# CH32X035G8U6-R0.net
KiCad netlist of a schematic drawn in Altium Designer
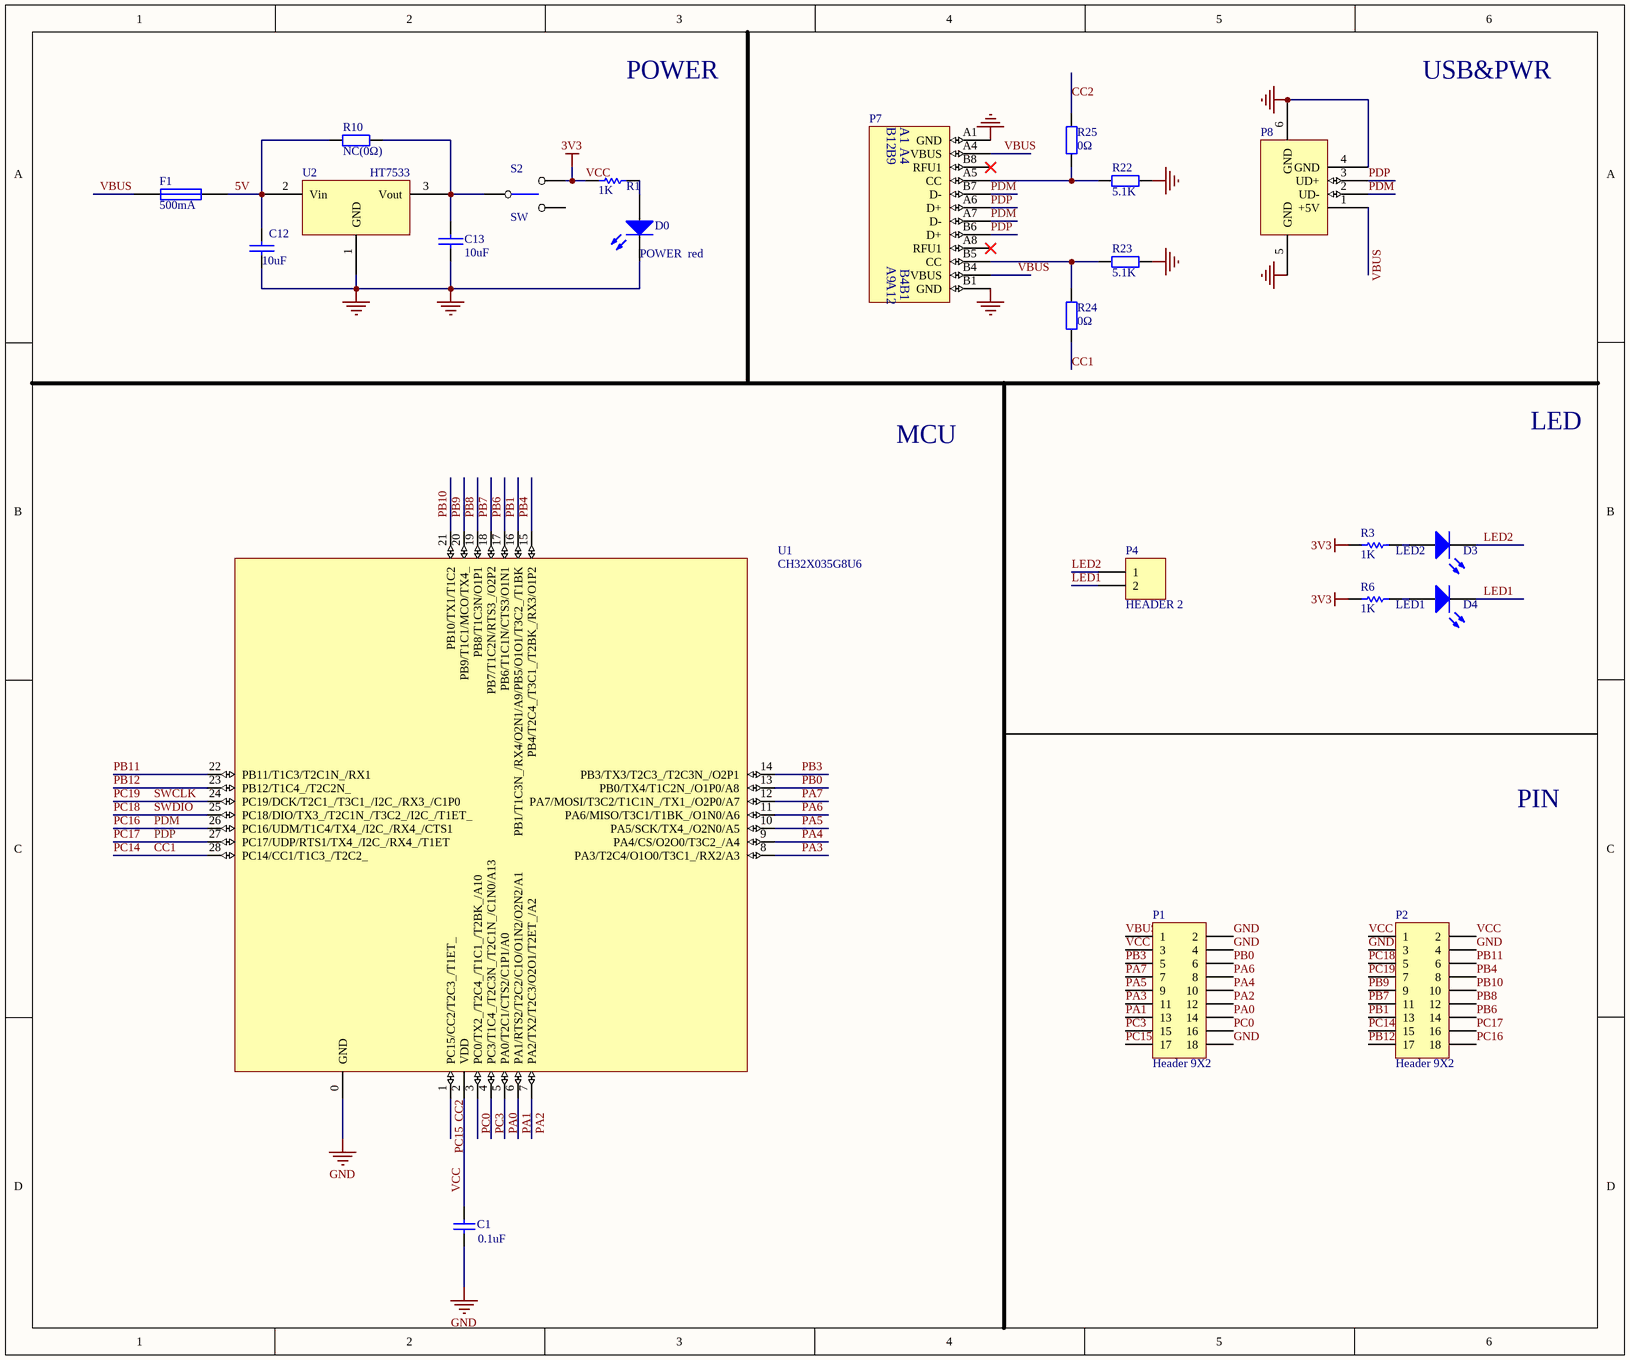
[diagram p0: CH32X035G8U6-R0.SchDoc]

(export (version "E")
  (design (tool "Eeschema 10.0.6"))
  (components
    (comp (ref "C1")
      (value "0.1uF")
      (footprint "0603_C")
      (description "Capacitor")
      (libsource (lib "Miscellaneous Devices") (part "Cap"))
    )
    (comp (ref "C12")
      (value "10uF")
      (footprint "0603_C")
      (description "Capacitor")
      (libsource (lib "*") (part "CAP"))
    )
    (comp (ref "C13")
      (value "10uF")
      (footprint "0603_C")
      (description "Capacitor")
      (libsource (lib "*") (part "CAP"))
    )
    (comp (ref "D0")
      (value "POWER  red")
      (footprint "0603+")
      (description "Typical INFRARED GaAs LED")
      (fields (field (name "PUBLISHER") "Altium Limited"))
      (libsource (lib "*") (part "LED0"))
    )
    (comp (ref "D3")
      (value "LED2")
      (footprint "0603+")
      (description "Typical INFRARED GaAs LED")
      (fields (field (name "PUBLISHER") "Altium Limited"))
      (libsource (lib "*") (part "LED0"))
    )
    (comp (ref "D4")
      (value "LED1")
      (footprint "0603+")
      (description "Typical INFRARED GaAs LED")
      (fields (field (name "PUBLISHER") "Altium Limited"))
      (libsource (lib "*") (part "LED0"))
    )
    (comp (ref "F1")
      (value "500mA")
      (footprint "0603")
      (description "Fuse")
      (libsource (lib "*") (part "FUSE1"))
    )
    (comp (ref "P1")
      (value "Header 9X2")
      (footprint "IDC18-2.54mm")
      (description "Header, 9-Pin, Dual row")
      (fields (field (name "PUBLISHER") "Altium Limited"))
      (libsource (lib "Miscellaneous Connectors") (part "Header 9X2"))
    )
    (comp (ref "P2")
      (value "Header 9X2")
      (footprint "IDC18-2.54mm")
      (description "Header, 9-Pin, Dual row")
      (fields (field (name "PUBLISHER") "Altium Limited"))
      (libsource (lib "Miscellaneous Connectors") (part "Header 9X2"))
    )
    (comp (ref "P4")
      (value "HEADER 2")
      (footprint "MYPCB:SIP2-2.54mm")
      (description "Header, 2-Pin")
      (libsource (lib "wch_sch_others") (part "HEADER 2"))
    )
    (comp (ref "P7")
      (value "TYPE-C")
      (footprint "TYPE-C-Receptacle-2.0")
      (libsource (lib "*") (part "TYPE-C1"))
    )
    (comp (ref "P8")
      (value "USB_A")
      (footprint "USBAF")
      (description "USB Port")
      (libsource (lib "*") (part "USB"))
    )
    (comp (ref "R1")
      (value "1K")
      (footprint "0603")
      (description "Semiconductor Resistor")
      (fields (field (name "PUBLISHER") "Altium Limited"))
      (libsource (lib "*") (part "Res Semi"))
    )
    (comp (ref "R3")
      (value "1K")
      (footprint "0603")
      (description "Semiconductor Resistor")
      (fields (field (name "PUBLISHER") "Altium Limited"))
      (libsource (lib "*") (part "Res Semi"))
    )
    (comp (ref "R6")
      (value "1K")
      (footprint "0603")
      (description "Semiconductor Resistor")
      (fields (field (name "PUBLISHER") "Altium Limited"))
      (libsource (lib "*") (part "Res Semi"))
    )
    (comp (ref "R10")
      (value "NC(0Ω)")
      (footprint "0603")
      (description "Resistor")
      (fields (field (name "PUBLISHER") "Altium Limited"))
      (libsource (lib "*") (part "Res2"))
    )
    (comp (ref "R22")
      (value "5.1K")
      (footprint "0603")
      (description "Resistor")
      (libsource (lib "") (part "Res2_1"))
    )
    (comp (ref "R23")
      (value "5.1K")
      (footprint "0603")
      (description "Resistor")
      (libsource (lib "") (part "Res2_1"))
    )
    (comp (ref "R24")
      (value "0Ω")
      (footprint "0603")
      (description "Resistor")
      (libsource (lib "Miscellaneous Devices") (part "Res2"))
    )
    (comp (ref "R25")
      (value "0Ω")
      (footprint "0603")
      (description "Resistor")
      (libsource (lib "Miscellaneous Devices") (part "Res2"))
    )
    (comp (ref "S2") (value "SW") (footprint "SW1") (libsource (lib "*") (part "SW")))
    (comp (ref "U1")
      (value "CH32X035G8U6")
      (footprint "QFN28_4X4")
      (description "RISC-V MCU with USB/PD/ADC/SPI/I2C/UART/OA/CMP")
      (libsource (lib "CHXXX") (part "CH32X035G8U6"))
    )
    (comp (ref "U2")
      (value "HT7533")
      (footprint "SOT-89")
      (libsource (lib "wch_sch_others") (part "1117-3.3V"))
    )
  )
  (nets
    (net (code "1") (name "/5V") (class "Default")
      (node (ref "C12") (pin "1") (pinfunction "1_1") (pintype "passive"))
      (node (ref "F1") (pin "2") (pinfunction "2_2") (pintype "passive"))
      (node (ref "R10") (pin "2") (pinfunction "2_2") (pintype "passive"))
      (node (ref "U2") (pin "2") (pinfunction "Vin_2") (pintype "passive"))
    )
    (net (code "3") (name "/CC1") (class "Default")
      (node (ref "P2") (pin "15") (pinfunction "15_15") (pintype "passive"))
      (node (ref "R24") (pin "1") (pinfunction "1_1") (pintype "passive"))
      (node (ref "U1") (pin "28") (pinfunction "PC14/CC1/T1C3_/T2C2__28") (pintype "bidirectional"))
    )
    (net (code "4") (name "/CC2") (class "Default")
      (node (ref "P1") (pin "17") (pinfunction "17_17") (pintype "passive"))
      (node (ref "R25") (pin "2") (pinfunction "2_2") (pintype "passive"))
      (node (ref "U1") (pin "1") (pinfunction "PC15/CC2/T2C3_/T1ET__1") (pintype "bidirectional"))
    )
    (net (code "5") (name "/LED1") (class "Default")
      (node (ref "D4") (pin "2") (pinfunction "K_2") (pintype "passive"))
      (node (ref "P4") (pin "2") (pinfunction "2_2") (pintype "passive"))
    )
    (net (code "6") (name "/LED2") (class "Default")
      (node (ref "D3") (pin "2") (pinfunction "K_2") (pintype "passive"))
      (node (ref "P4") (pin "1") (pinfunction "1_1") (pintype "passive"))
    )
    (net (code "7") (name "/PA0") (class "Default")
      (node (ref "P1") (pin "14") (pinfunction "14_14") (pintype "passive"))
      (node (ref "U1") (pin "5") (pinfunction "PA0/T2C1/CTS2/C1P1/A0_5") (pintype "bidirectional"))
    )
    (net (code "8") (name "/PA1") (class "Default")
      (node (ref "P1") (pin "13") (pinfunction "13_13") (pintype "passive"))
      (node (ref "U1") (pin "6") (pinfunction "PA1/RTS2/T2C2/C1O/O1N2/O2N2/A1_6") (pintype "bidirectional"))
    )
    (net (code "9") (name "/PA2") (class "Default")
      (node (ref "P1") (pin "12") (pinfunction "12_12") (pintype "passive"))
      (node (ref "U1") (pin "7") (pinfunction "PA2/TX2/T2C3/O2O1/T2ET_/A2_7") (pintype "bidirectional"))
    )
    (net (code "10") (name "/PA3") (class "Default")
      (node (ref "P1") (pin "11") (pinfunction "11_11") (pintype "passive"))
      (node (ref "U1") (pin "8") (pinfunction "PA3/T2C4/O1O0/T3C1_/RX2/A3_8") (pintype "bidirectional"))
    )
    (net (code "11") (name "/PA4") (class "Default")
      (node (ref "P1") (pin "10") (pinfunction "10_10") (pintype "passive"))
      (node (ref "U1") (pin "9") (pinfunction "PA4/CS/O2O0/T3C2_/A4_9") (pintype "bidirectional"))
    )
    (net (code "12") (name "/PA5") (class "Default")
      (node (ref "P1") (pin "9") (pinfunction "9_9") (pintype "passive"))
      (node (ref "U1") (pin "10") (pinfunction "PA5/SCK/TX4_/O2N0/A5_10") (pintype "bidirectional"))
    )
    (net (code "13") (name "/PA6") (class "Default")
      (node (ref "P1") (pin "8") (pinfunction "8_8") (pintype "passive"))
      (node (ref "U1") (pin "11") (pinfunction "PA6/MISO/T3C1/T1BK_/O1N0/A6_11") (pintype "bidirectional"))
    )
    (net (code "14") (name "/PA7") (class "Default")
      (node (ref "P1") (pin "7") (pinfunction "7_7") (pintype "passive"))
      (node (ref "U1") (pin "12") (pinfunction "PA7/MOSI/T3C2/T1C1N_/TX1_/O2P0/A7_12") (pintype "bidirectional"))
    )
    (net (code "15") (name "/PB0") (class "Default")
      (node (ref "P1") (pin "6") (pinfunction "6_6") (pintype "passive"))
      (node (ref "U1") (pin "13") (pinfunction "PB0/TX4/T1C2N_/O1P0/A8_13") (pintype "bidirectional"))
    )
    (net (code "16") (name "/PB1") (class "Default")
      (node (ref "P2") (pin "13") (pinfunction "13_13") (pintype "passive"))
      (node (ref "U1") (pin "16") (pinfunction "PB1/T1C3N_/RX4/O2N1/A9/PB5/O1O1/T3C2_/T1BK_16") (pintype "bidirectional"))
    )
    (net (code "17") (name "/PB3") (class "Default")
      (node (ref "P1") (pin "5") (pinfunction "5_5") (pintype "passive"))
      (node (ref "U1") (pin "14") (pinfunction "PB3/TX3/T2C3_/T2C3N_/O2P1_14") (pintype "bidirectional"))
    )
    (net (code "18") (name "/PB4") (class "Default")
      (node (ref "P2") (pin "8") (pinfunction "8_8") (pintype "passive"))
      (node (ref "U1") (pin "15") (pinfunction "PB4/T2C4_/T3C1_/T2BK_/RX3/O1P2_15") (pintype "bidirectional"))
    )
    (net (code "19") (name "/PB6") (class "Default")
      (node (ref "P2") (pin "14") (pinfunction "14_14") (pintype "passive"))
      (node (ref "U1") (pin "17") (pinfunction "PB6/T1C1N/CTS3/O1N1_17") (pintype "bidirectional"))
    )
    (net (code "20") (name "/PB7") (class "Default")
      (node (ref "P2") (pin "11") (pinfunction "11_11") (pintype "passive"))
      (node (ref "U1") (pin "18") (pinfunction "PB7/T1C2N/RTS3_/O2P2_18") (pintype "bidirectional"))
    )
    (net (code "21") (name "/PB8") (class "Default")
      (node (ref "P2") (pin "12") (pinfunction "12_12") (pintype "passive"))
      (node (ref "U1") (pin "19") (pinfunction "PB8/T1C3N/O1P1_19") (pintype "bidirectional"))
    )
    (net (code "22") (name "/PB9") (class "Default")
      (node (ref "P2") (pin "9") (pinfunction "9_9") (pintype "passive"))
      (node (ref "U1") (pin "20") (pinfunction "PB9/T1C1/MCO/TX4__20") (pintype "bidirectional"))
    )
    (net (code "23") (name "/PB10") (class "Default")
      (node (ref "P2") (pin "10") (pinfunction "10_10") (pintype "passive"))
      (node (ref "U1") (pin "21") (pinfunction "PB10/TX1/T1C2_21") (pintype "bidirectional"))
    )
    (net (code "24") (name "/PB11") (class "Default")
      (node (ref "P2") (pin "6") (pinfunction "6_6") (pintype "passive"))
      (node (ref "U1") (pin "22") (pinfunction "PB11/T1C3/T2C1N_/RX1_22") (pintype "bidirectional"))
    )
    (net (code "25") (name "/PB12") (class "Default")
      (node (ref "P2") (pin "17") (pinfunction "17_17") (pintype "passive"))
      (node (ref "U1") (pin "23") (pinfunction "PB12/T1C4_/T2C2N__23") (pintype "bidirectional"))
    )
    (net (code "26") (name "/PC0") (class "Default")
      (node (ref "P1") (pin "16") (pinfunction "16_16") (pintype "passive"))
      (node (ref "U1") (pin "3") (pinfunction "PC0/TX2_/T2C4_/T1C1_/T2BK_/A10_3") (pintype "bidirectional"))
    )
    (net (code "27") (name "/PC3") (class "Default")
      (node (ref "P1") (pin "15") (pinfunction "15_15") (pintype "passive"))
      (node (ref "U1") (pin "4") (pinfunction "PC3/T1C4_/T2C3N_/T2C1N_/C1N0/A13_4") (pintype "bidirectional"))
    )
    (net (code "28") (name "/PC16") (class "Default")
      (node (ref "P2") (pin "18") (pinfunction "18_18") (pintype "passive"))
      (node (ref "P7") (pin "A7") (pinfunction "D-_A7") (pintype "bidirectional"))
      (node (ref "P7") (pin "B7") (pinfunction "D-_B7") (pintype "bidirectional"))
      (node (ref "P8") (pin "2") (pinfunction "UD-_2") (pintype "bidirectional"))
      (node (ref "U1") (pin "26") (pinfunction "PC16/UDM/T1C4/TX4_/I2C_/RX4_/CTS1_26") (pintype "bidirectional"))
    )
    (net (code "29") (name "/PC17") (class "Default")
      (node (ref "P2") (pin "16") (pinfunction "16_16") (pintype "passive"))
      (node (ref "P7") (pin "A6") (pinfunction "D+_A6") (pintype "bidirectional"))
      (node (ref "P7") (pin "B6") (pinfunction "D+_B6") (pintype "bidirectional"))
      (node (ref "P8") (pin "3") (pinfunction "UD+_3") (pintype "bidirectional"))
      (node (ref "U1") (pin "27") (pinfunction "PC17/UDP/RTS1/TX4_/I2C_/RX4_/T1ET_27") (pintype "bidirectional"))
    )
    (net (code "30") (name "/PC18") (class "Default")
      (node (ref "P2") (pin "5") (pinfunction "5_5") (pintype "passive"))
      (node (ref "U1") (pin "25") (pinfunction "PC18/DIO/TX3_/T2C1N_/T3C2_/I2C_/T1ET__25") (pintype "bidirectional"))
    )
    (net (code "31") (name "/PC19") (class "Default")
      (node (ref "P2") (pin "7") (pinfunction "7_7") (pintype "passive"))
      (node (ref "U1") (pin "24") (pinfunction "PC19/DCK/T2C1_/T3C1_/I2C_/RX3_/C1P0_24") (pintype "bidirectional"))
    )
    (net (code "32") (name "/VBUS") (class "Default")
      (node (ref "F1") (pin "1") (pinfunction "1_1") (pintype "passive"))
      (node (ref "P1") (pin "1") (pinfunction "1_1") (pintype "passive"))
      (node (ref "P7") (pin "A4") (pinfunction "VBUS_A4") (pintype "bidirectional"))
      (node (ref "P7") (pin "B4") (pinfunction "VBUS_B4") (pintype "bidirectional"))
      (node (ref "P8") (pin "1") (pinfunction "+5V_1") (pintype "power_in"))
    )
    (net (code "33") (name "3V3") (class "Default")
      (node (ref "C1") (pin "2") (pinfunction "2_2") (pintype "passive"))
      (node (ref "P1") (pin "3") (pinfunction "3_3") (pintype "passive"))
      (node (ref "P2") (pin "1") (pinfunction "1_1") (pintype "passive"))
      (node (ref "P2") (pin "2") (pinfunction "2_2") (pintype "passive"))
      (node (ref "R1") (pin "2") (pinfunction "2_2") (pintype "passive"))
      (node (ref "R3") (pin "1") (pinfunction "1_1") (pintype "passive"))
      (node (ref "R6") (pin "1") (pinfunction "1_1") (pintype "passive"))
      (node (ref "S2") (pin "3") (pinfunction "3_3") (pintype "passive"))
      (node (ref "U1") (pin "2") (pinfunction "VDD_2") (pintype "power_in"))
    )
    (net (code "34") (name "GND") (class "Default")
      (node (ref "C1") (pin "1") (pinfunction "1_1") (pintype "passive"))
      (node (ref "C12") (pin "2") (pinfunction "2_2") (pintype "passive"))
      (node (ref "C13") (pin "2") (pinfunction "2_2") (pintype "passive"))
      (node (ref "D0") (pin "2") (pinfunction "K_2") (pintype "passive"))
      (node (ref "P1") (pin "18") (pinfunction "18_18") (pintype "passive"))
      (node (ref "P1") (pin "2") (pinfunction "2_2") (pintype "passive"))
      (node (ref "P1") (pin "4") (pinfunction "4_4") (pintype "passive"))
      (node (ref "P2") (pin "3") (pinfunction "3_3") (pintype "passive"))
      (node (ref "P2") (pin "4") (pinfunction "4_4") (pintype "passive"))
      (node (ref "P7") (pin "A1") (pinfunction "GND_A1") (pintype "bidirectional"))
      (node (ref "P7") (pin "B1") (pinfunction "GND_B1") (pintype "bidirectional"))
      (node (ref "P8") (pin "4") (pinfunction "GND_4") (pintype "power_in"))
      (node (ref "P8") (pin "5") (pinfunction "GND_5") (pintype "power_in"))
      (node (ref "P8") (pin "6") (pinfunction "GND_6") (pintype "power_in"))
      (node (ref "R22") (pin "2") (pinfunction "2_2") (pintype "passive"))
      (node (ref "R23") (pin "2") (pinfunction "2_2") (pintype "passive"))
      (node (ref "U1") (pin "0") (pinfunction "GND_0") (pintype "power_in"))
      (node (ref "U2") (pin "1") (pinfunction "GND_1") (pintype "passive"))
    )
    (net (code "35") (name "Net-(D0-A)") (class "Default")
      (node (ref "D0") (pin "1") (pinfunction "A_1") (pintype "passive"))
      (node (ref "R1") (pin "1") (pinfunction "1_1") (pintype "passive"))
    )
    (net (code "36") (name "Net-(D3-A)") (class "Default")
      (node (ref "D3") (pin "1") (pinfunction "A_1") (pintype "passive"))
      (node (ref "R3") (pin "2") (pinfunction "2_2") (pintype "passive"))
    )
    (net (code "37") (name "Net-(D4-A)") (class "Default")
      (node (ref "D4") (pin "1") (pinfunction "A_1") (pintype "passive"))
      (node (ref "R6") (pin "2") (pinfunction "2_2") (pintype "passive"))
    )
    (net (code "38") (name "Net-(P7-CC-PadA5)") (class "Default")
      (node (ref "P7") (pin "A5") (pinfunction "CC_A5") (pintype "bidirectional"))
      (node (ref "R22") (pin "1") (pinfunction "1_1") (pintype "passive"))
      (node (ref "R25") (pin "1") (pinfunction "1_1") (pintype "passive"))
    )
    (net (code "39") (name "Net-(P7-CC-PadB5)") (class "Default")
      (node (ref "P7") (pin "B5") (pinfunction "CC_B5") (pintype "bidirectional"))
      (node (ref "R23") (pin "1") (pinfunction "1_1") (pintype "passive"))
      (node (ref "R24") (pin "2") (pinfunction "2_2") (pintype "passive"))
    )
    (net (code "40") (name "Net-(U2-Vout)") (class "Default")
      (node (ref "C13") (pin "1") (pinfunction "1_1") (pintype "passive"))
      (node (ref "R10") (pin "1") (pinfunction "1_1") (pintype "passive"))
      (node (ref "S2") (pin "1") (pinfunction "1_1") (pintype "passive"))
      (node (ref "U2") (pin "3") (pinfunction "Vout_3") (pintype "passive"))
    )
    (net (code "41") (name "unconnected-(P7-RFU1-PadA8)") (class "Default")
      (node (ref "P7") (pin "A8") (pinfunction "RFU1_A8") (pintype "bidirectional+no_connect"))
    )
    (net (code "42") (name "unconnected-(P7-RFU1-PadB8)") (class "Default")
      (node (ref "P7") (pin "B8") (pinfunction "RFU1_B8") (pintype "bidirectional+no_connect"))
    )
    (net (code "43") (name "unconnected-(S2-Pad2)") (class "Default")
      (node (ref "S2") (pin "2") (pinfunction "2_2") (pintype "passive"))
    )
  )
)
